# Auxboardone.net
KiCad netlist of a schematic drawn in Altium Designer
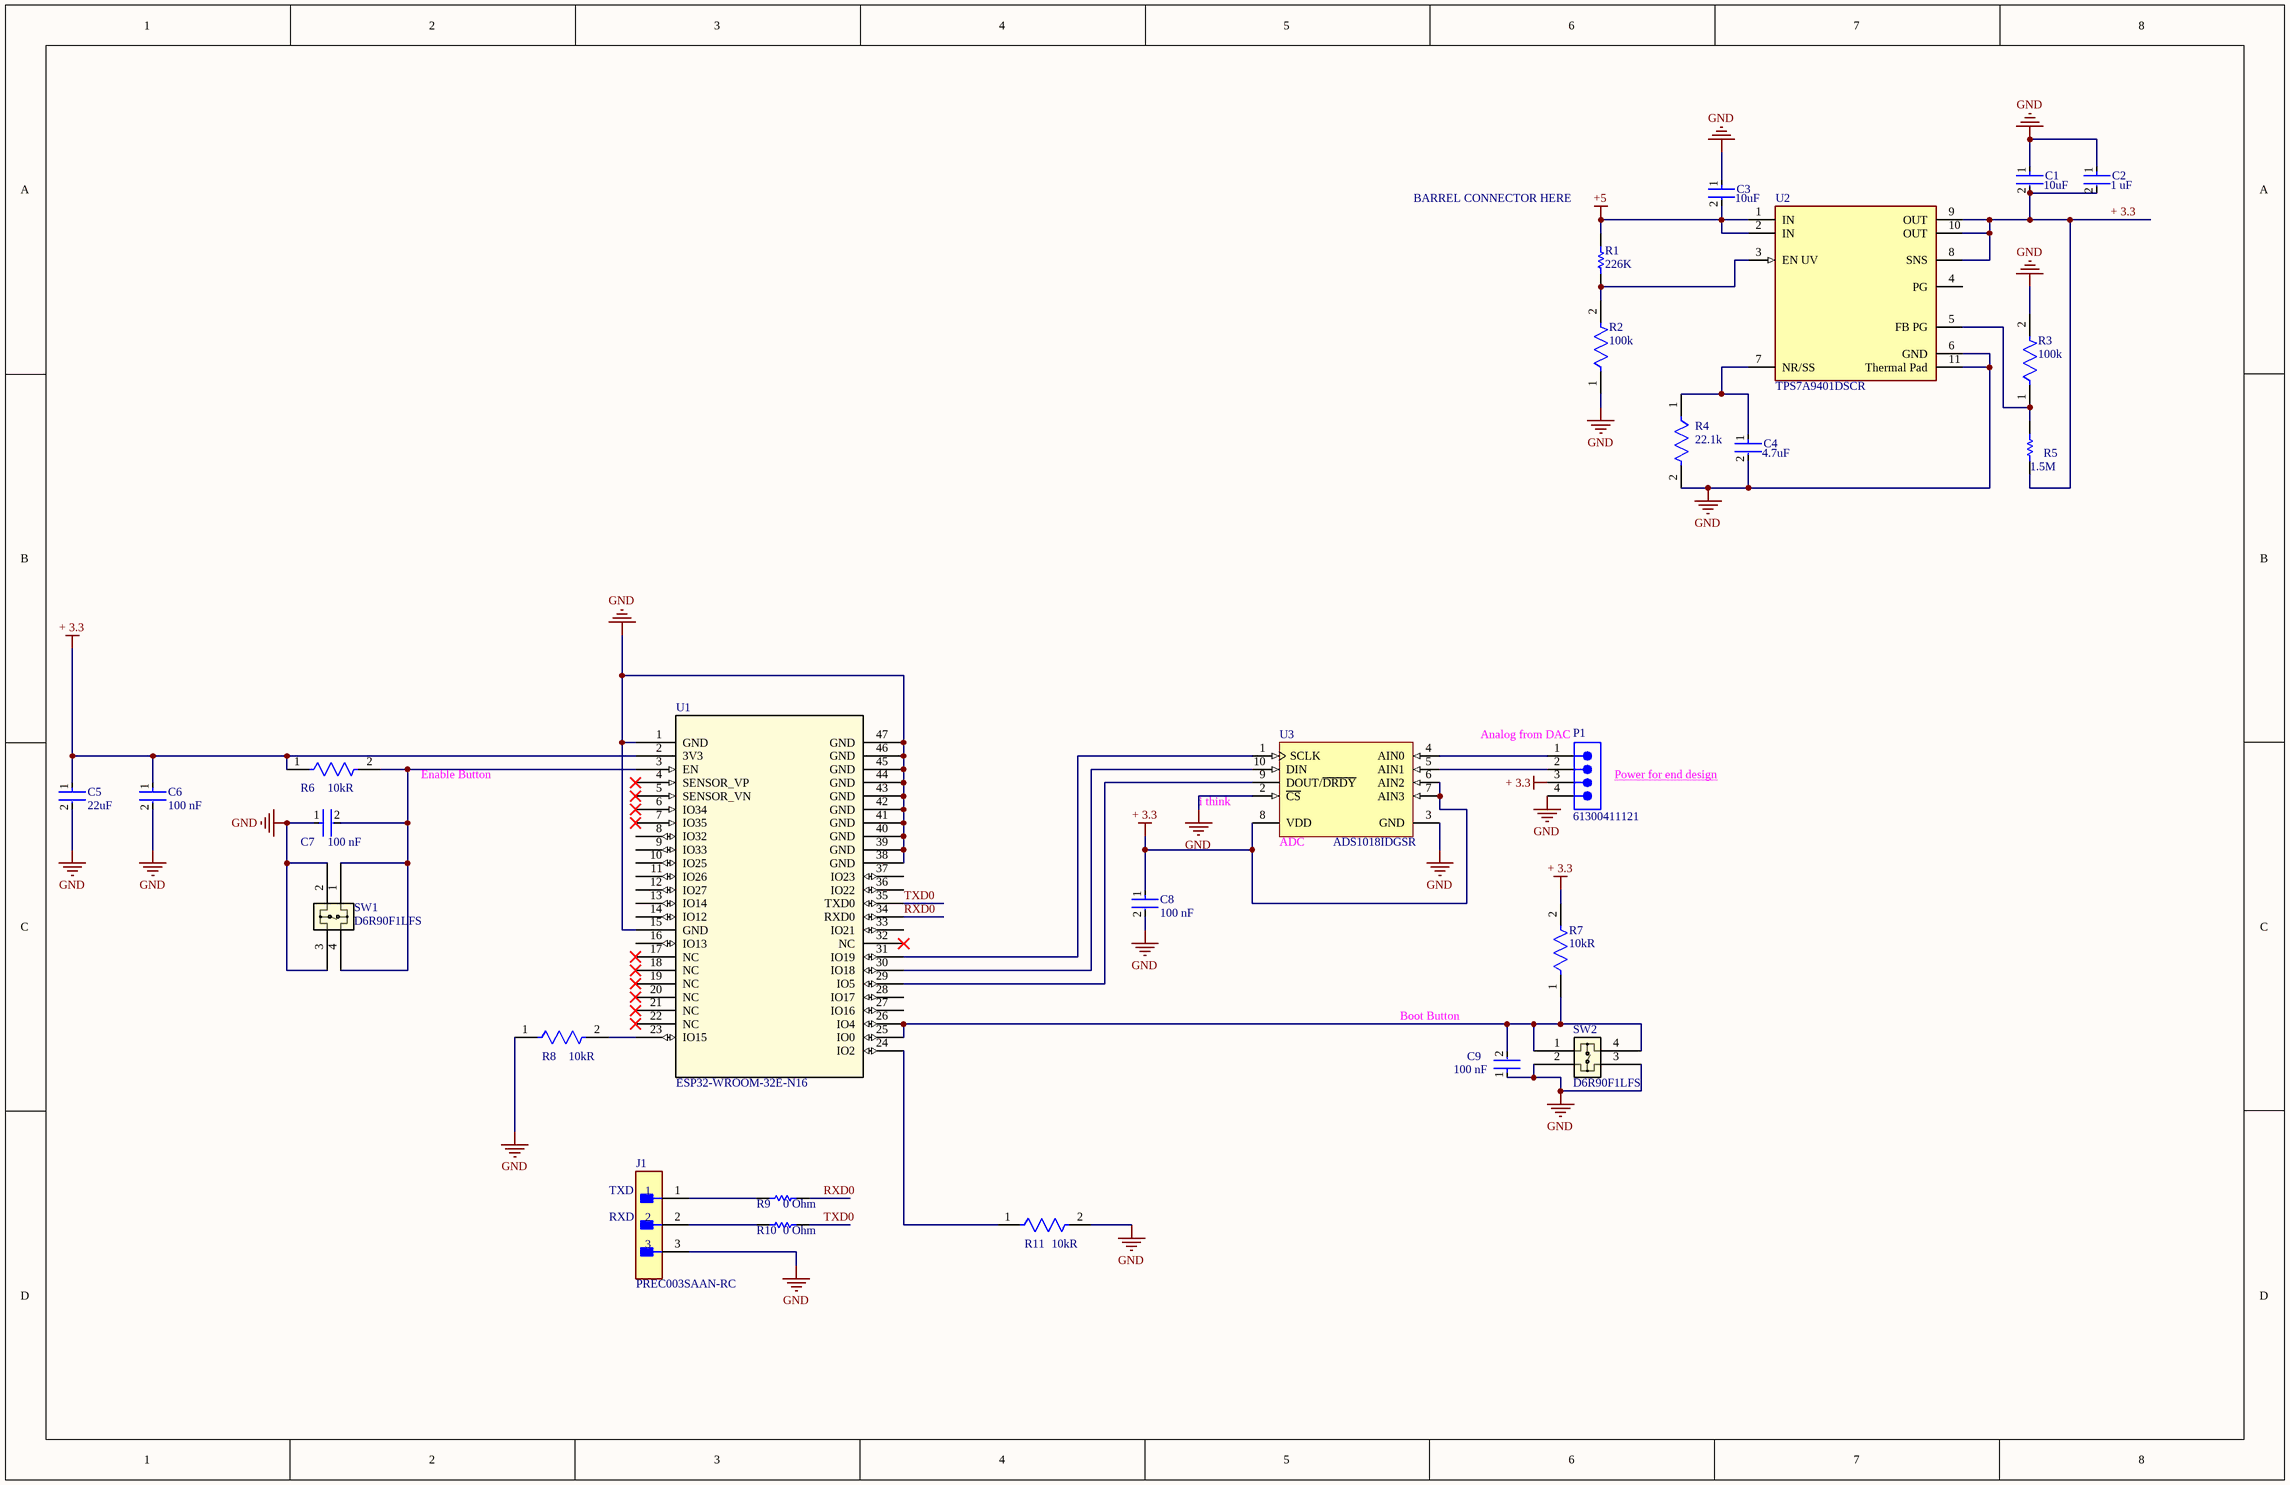
[diagram p0: Auxboardone.SchDoc]

(export (version "E")
  (design (tool "Eeschema 10.0.6"))
  (components
    (comp (ref "C1")
      (value "CL21A106KOQNNNE")
      (footprint "FP-CL21-IPC_B")
      (description "CL21 Series 0805 10uF 16V ±10% Tolerance X5R Multilayer Ceramic Chip Capacitor")
      (fields
        (field (name "VOLTAGE") "16V")
        (field (name "CAPACITANCE") "10uF")
        (field (name "TOLERANCE") "10%")
      )
      (libsource (lib "Altium Content Vault") (part "b4654b650e69147ec39a6b967a45e02"))
    )
    (comp (ref "C2")
      (value "CC0805KKX7R7BB105")
      (footprint "FP-CC0805-0_85-MFG")
      (description "CC0805 1 uF X7R 10.00% 16 V")
      (fields (field (name "CAPACITANCE") "1 uF") (field (name "MANUFACTURER") "Yageo"))
      (libsource (lib "Altium Content Vault") (part "11868f565c42a9108669ba33697ecf6"))
    )
    (comp (ref "C3")
      (value "CL21A106KOQNNNE")
      (footprint "FP-CL21-IPC_B")
      (description "CL21 Series 0805 10uF 16V ±10% Tolerance X5R Multilayer Ceramic Chip Capacitor")
      (fields
        (field (name "VOLTAGE") "16V")
        (field (name "CAPACITANCE") "10uF")
        (field (name "TOLERANCE") "10%")
      )
      (libsource (lib "Altium Content Vault") (part "b4654b650e69147ec39a6b967a45e02"))
    )
    (comp (ref "C4")
      (value "CL21A475KAQNNNE")
      (footprint "FP-CL21-IPC_A")
      (description "CL21 Series 0805 4.7uF 25V ±10% Tolerance X5R Multilayer Ceramic Chip Capacitor")
      (fields (field (name "CAPACITANCE") "4.7uF") (field (name "TOLERANCE") "10%"))
      (libsource (lib "Altium Content Vault") (part "b4654b650e69147ec39a6b967a45e02"))
    )
    (comp (ref "C5")
      (value "CL21A226MQQNNNE")
      (footprint "FP-CL21-IPC_A")
      (description "CL21 Series 0805 22uF 6.3V ±20% Tolerance X5R Multilayer Ceramic Chip Capacitor")
      (fields (field (name "CAPACITANCE") "22uF") (field (name "TOLERANCE") "20%"))
      (libsource (lib "Altium Content Vault") (part "b4654b650e69147ec39a6b967a45e02"))
    )
    (comp (ref "C6")
      (value "CC0805KRX7R9BB104")
      (footprint "FP-CC0805-0_85-MFG")
      (description "CAP CER 0.1UF 50V X7R 0805")
      (fields
        (field (name "TOLERANCE") "0.1")
        (field (name "CAPACITANCE") "100 nF")
        (field (name "MANUFACTURER") "Yageo")
      )
      (libsource (lib "Altium Content Vault") (part "11868f565c42a9108669ba33697ecf6"))
    )
    (comp (ref "C7")
      (value "CC0805KRX7R9BB104")
      (footprint "FP-CC0805-0_85-MFG")
      (description "CAP CER 0.1UF 50V X7R 0805")
      (fields
        (field (name "TOLERANCE") "0.1")
        (field (name "CAPACITANCE") "100 nF")
        (field (name "MANUFACTURER") "Yageo")
      )
      (libsource (lib "Altium Content Vault") (part "11868f565c42a9108669ba33697ecf6"))
    )
    (comp (ref "C8")
      (value "CC0805KRX7R9BB104")
      (footprint "FP-CC0805-0_85-MFG")
      (description "CAP CER 0.1UF 50V X7R 0805")
      (fields
        (field (name "TOLERANCE") "0.1")
        (field (name "CAPACITANCE") "100 nF")
        (field (name "MANUFACTURER") "Yageo")
      )
      (libsource (lib "Altium Content Vault") (part "11868f565c42a9108669ba33697ecf6"))
    )
    (comp (ref "C9")
      (value "CC0805KRX7R9BB104")
      (footprint "FP-CC0805-0_85-MFG")
      (description "CAP CER 0.1UF 50V X7R 0805")
      (fields
        (field (name "TOLERANCE") "0.1")
        (field (name "CAPACITANCE") "100 nF")
        (field (name "MANUFACTURER") "Yageo")
      )
      (libsource (lib "Altium Content Vault") (part "11868f565c42a9108669ba33697ecf6"))
    )
    (comp (ref "J1")
      (value "PREC003SAAN-RC")
      (footprint "FP-PREC003SAAN-RC-MFG")
      (description "PREC003SAAN-RC Conn Header Vert 3POS 2.54MM")
      (libsource (lib "Altium Content Vault") (part "0d3f023dd272f625e17a2be33dea85f"))
    )
    (comp (ref "P1")
      (value "61300411121")
      (footprint "61300411121")
      (libsource (lib "Altium Content Vault") (part "Header_Male_1R_04P"))
    )
    (comp (ref "R1")
      (value "RC0805FR-07226KL")
      (footprint "RESC2013X60X35LL10T20")
      (fields (field (name "MANUFACTURER") "Yageo") (field (name "RESISTANCE") "226K"))
      (libsource (lib "Altium Content Vault") (part "RES"))
    )
    (comp (ref "R2")
      (value "RC0805FR-07100KL")
      (footprint "FP-RC0805-0_6-IPC_C")
      (description "RES 100K OHM 1% 1/8W 0805")
      (fields (field (name "TOLERANCE") "1%") (field (name "RESISTANCE") "100k"))
      (libsource (lib "Altium Content Vault") (part "1029c3af85768c4190bb7ad29bc67b5"))
    )
    (comp (ref "R3")
      (value "RC0805FR-07100KL")
      (footprint "FP-RC0805-0_6-IPC_C")
      (description "RES 100K OHM 1% 1/8W 0805")
      (fields (field (name "TOLERANCE") "1%") (field (name "RESISTANCE") "100k"))
      (libsource (lib "Altium Content Vault") (part "1029c3af85768c4190bb7ad29bc67b5"))
    )
    (comp (ref "R4")
      (value "RMCF0805FT22K1")
      (footprint "FP-RMCF0805-IPC_B")
      (description "22.1kΩ ±1% 0.125W 0805 Thick Film Chip Resistor AEC-Q200 compliant")
      (fields (field (name "RESISTANCE") "22.1k") (field (name "TOLERANCE") "1%"))
      (libsource (lib "Altium Content Vault") (part "1029c3af85768c4190bb7ad29bc67b5"))
    )
    (comp (ref "R5")
      (value "1.5M")
      (footprint "RESC0805(2012)_N")
      (description "1M5 0.125W 5% 0805 (2012 Metric)  SMD")
      (fields (field (name "TOLERANCE") "5 %") (field (name "POWER") "0.125 W"))
      (libsource (lib "Altium Content Vault") (part "RES"))
    )
    (comp (ref "R6")
      (value "RR1220P-103-D")
      (footprint "FP-RR1220-IPC_A")
      (description "10kΩ ±0.5% 0.1W 1/10W Chip Resistor 0805 (2012 Metric) Thin Film")
      (fields (field (name "RESISTANCE") "10kR") (field (name "TOLERANCE") "0.5%"))
      (libsource (lib "Altium Content Vault") (part "1029c3af85768c4190bb7ad29bc67b5"))
    )
    (comp (ref "R7")
      (value "RR1220P-103-D")
      (footprint "FP-RR1220-IPC_A")
      (description "10kΩ ±0.5% 0.1W 1/10W Chip Resistor 0805 (2012 Metric) Thin Film")
      (fields (field (name "RESISTANCE") "10kR") (field (name "TOLERANCE") "0.5%"))
      (libsource (lib "Altium Content Vault") (part "1029c3af85768c4190bb7ad29bc67b5"))
    )
    (comp (ref "R8")
      (value "RR1220P-103-D")
      (footprint "FP-RR1220-IPC_A")
      (description "10kΩ ±0.5% 0.1W 1/10W Chip Resistor 0805 (2012 Metric) Thin Film")
      (fields (field (name "RESISTANCE") "10kR") (field (name "TOLERANCE") "0.5%"))
      (libsource (lib "Altium Content Vault") (part "1029c3af85768c4190bb7ad29bc67b5"))
    )
    (comp (ref "R9")
      (value "ERJ-6GEY0R00V")
      (footprint "RESC2013X70X40NL20T20")
      (description "Chip Resistor, 0 Ohm, +/- 1%, 0.125 W, -55 to 155 degC, 0805 (2012 Metric), RoHS, Tape and Reel")
      (fields (field (name "TOLERANCE") "5%") (field (name "RESISTANCE") "0 Ohm"))
      (libsource (lib "Altium Content Vault") (part "RES-2"))
    )
    (comp (ref "R10")
      (value "ERJ-6GEY0R00V")
      (footprint "RESC2013X70X40NL20T20")
      (description "Chip Resistor, 0 Ohm, +/- 1%, 0.125 W, -55 to 155 degC, 0805 (2012 Metric), RoHS, Tape and Reel")
      (fields (field (name "TOLERANCE") "5%") (field (name "RESISTANCE") "0 Ohm"))
      (libsource (lib "Altium Content Vault") (part "RES-2"))
    )
    (comp (ref "R11")
      (value "RR1220P-103-D")
      (footprint "FP-RR1220-IPC_A")
      (description "10kΩ ±0.5% 0.1W 1/10W Chip Resistor 0805 (2012 Metric) Thin Film")
      (fields (field (name "RESISTANCE") "10kR") (field (name "TOLERANCE") "0.5%"))
      (libsource (lib "Altium Content Vault") (part "1029c3af85768c4190bb7ad29bc67b5"))
    )
    (comp (ref "SW1")
      (value "D6R90F1LFS")
      (footprint "D6R_CNK")
      (description "No Description Available")
      (libsource (lib "") (part "D6R90F1LFS_1"))
    )
    (comp (ref "SW2")
      (value "D6R90F1LFS")
      (footprint "D6R_CNK")
      (description "No Description Available")
      (libsource (lib "Button") (part "D6R90F1LFS"))
    )
    (comp (ref "U1")
      (value "ESP32-WROOM-32E-N16")
      (footprint "ESP32-WROOM-32E_EXP")
      (description "No Description Available")
      (libsource (lib "ESP32-WROOM-32E-N16") (part "ESP32-WROOM-32E-N16"))
    )
    (comp (ref "U2")
      (value "TPS7A9401DSCR")
      (footprint "FP-DSC0010J-MFG")
      (description "1-A, ULTRA-LOW NOISE, ULTRA-HIGH")
      (libsource (lib "Altium Content Vault") (part "a6308bcaf518fe2c6c22e77077fd2b2"))
    )
    (comp (ref "U3")
      (value "ADS1018IDGSR")
      (footprint "TI-DGS10_N")
      (fields (field (name "MANUFACTURER") "Texas Instruments"))
      (libsource (lib "Altium Content Vault") (part "TI-ADS1X18XXX10"))
    )
  )
  (nets
    (net (code "1") (name "+ 3.3") (class "Default")
      (node (ref "C1") (pin "2") (pinfunction "2_2") (pintype "passive"))
      (node (ref "C2") (pin "2") (pinfunction "2_2") (pintype "passive"))
      (node (ref "C5") (pin "1") (pinfunction "1_1") (pintype "passive"))
      (node (ref "C6") (pin "1") (pinfunction "1_1") (pintype "passive"))
      (node (ref "C8") (pin "1") (pinfunction "1_1") (pintype "passive"))
      (node (ref "P1") (pin "3") (pinfunction "3_3") (pintype "passive"))
      (node (ref "R5") (pin "1") (pinfunction "1_1") (pintype "passive"))
      (node (ref "R6") (pin "1") (pinfunction "1_1") (pintype "passive"))
      (node (ref "R7") (pin "2") (pinfunction "2_2") (pintype "passive"))
      (node (ref "U1") (pin "2") (pinfunction "3V3_2") (pintype "power_in"))
      (node (ref "U2") (pin "10") (pinfunction "OUT_10") (pintype "power_in"))
      (node (ref "U2") (pin "8") (pinfunction "SNS_8") (pintype "passive"))
      (node (ref "U2") (pin "9") (pinfunction "OUT_9") (pintype "power_in"))
      (node (ref "U3") (pin "6") (pinfunction "AIN2_6") (pintype "input"))
      (node (ref "U3") (pin "7") (pinfunction "AIN3_7") (pintype "input"))
      (node (ref "U3") (pin "8") (pinfunction "VDD_8") (pintype "power_in"))
    )
    (net (code "2") (name "+5") (class "Default")
      (node (ref "C3") (pin "2") (pinfunction "2_2") (pintype "passive"))
      (node (ref "R1") (pin "2") (pinfunction "2_2") (pintype "passive"))
      (node (ref "U2") (pin "1") (pinfunction "IN_1") (pintype "power_in"))
      (node (ref "U2") (pin "2") (pinfunction "IN_2") (pintype "power_in"))
    )
    (net (code "3") (name "/RXD0") (class "Default")
      (node (ref "R9") (pin "2") (pinfunction "2_2") (pintype "passive"))
      (node (ref "U1") (pin "34") (pinfunction "RXD0_34") (pintype "bidirectional"))
    )
    (net (code "4") (name "/TXD0") (class "Default")
      (node (ref "R10") (pin "2") (pinfunction "2_2") (pintype "passive"))
      (node (ref "U1") (pin "35") (pinfunction "TXD0_35") (pintype "bidirectional"))
    )
    (net (code "5") (name "GND") (class "Default")
      (node (ref "C1") (pin "1") (pinfunction "1_1") (pintype "passive"))
      (node (ref "C2") (pin "1") (pinfunction "1_1") (pintype "passive"))
      (node (ref "C3") (pin "1") (pinfunction "1_1") (pintype "passive"))
      (node (ref "C4") (pin "2") (pinfunction "2_2") (pintype "passive"))
      (node (ref "C5") (pin "2") (pinfunction "2_2") (pintype "passive"))
      (node (ref "C6") (pin "2") (pinfunction "2_2") (pintype "passive"))
      (node (ref "C7") (pin "1") (pinfunction "1_1") (pintype "passive"))
      (node (ref "C8") (pin "2") (pinfunction "2_2") (pintype "passive"))
      (node (ref "C9") (pin "1") (pinfunction "1_1") (pintype "passive"))
      (node (ref "J1") (pin "3") (pinfunction "3_3") (pintype "passive"))
      (node (ref "P1") (pin "4") (pinfunction "4_4") (pintype "passive"))
      (node (ref "R11") (pin "2") (pinfunction "2_2") (pintype "passive"))
      (node (ref "R2") (pin "1") (pinfunction "1_1") (pintype "passive"))
      (node (ref "R3") (pin "2") (pinfunction "2_2") (pintype "passive"))
      (node (ref "R4") (pin "2") (pinfunction "2_2") (pintype "passive"))
      (node (ref "R8") (pin "1") (pinfunction "1_1") (pintype "passive"))
      (node (ref "SW1") (pin "2") (pinfunction "2_2") (pintype "passive"))
      (node (ref "SW1") (pin "3") (pinfunction "3_3") (pintype "passive"))
      (node (ref "SW2") (pin "2") (pinfunction "2_2") (pintype "passive"))
      (node (ref "SW2") (pin "3") (pinfunction "3_3") (pintype "passive"))
      (node (ref "U1") (pin "1") (pinfunction "GND_1") (pintype "power_in"))
      (node (ref "U1") (pin "15") (pinfunction "GND_15") (pintype "power_in"))
      (node (ref "U1") (pin "38") (pinfunction "GND_38") (pintype "power_in"))
      (node (ref "U1") (pin "39") (pinfunction "GND_39") (pintype "power_in"))
      (node (ref "U1") (pin "40") (pinfunction "GND_40") (pintype "power_in"))
      (node (ref "U1") (pin "41") (pinfunction "GND_41") (pintype "power_in"))
      (node (ref "U1") (pin "42") (pinfunction "GND_42") (pintype "power_in"))
      (node (ref "U1") (pin "43") (pinfunction "GND_43") (pintype "power_in"))
      (node (ref "U1") (pin "44") (pinfunction "GND_44") (pintype "power_in"))
      (node (ref "U1") (pin "45") (pinfunction "GND_45") (pintype "power_in"))
      (node (ref "U1") (pin "46") (pinfunction "GND_46") (pintype "power_in"))
      (node (ref "U1") (pin "47") (pinfunction "GND_47") (pintype "power_in"))
      (node (ref "U2") (pin "11") (pinfunction "Thermal_Pad_11") (pintype "power_in"))
      (node (ref "U2") (pin "6") (pinfunction "GND_6") (pintype "power_in"))
      (node (ref "U3") (pin "2") (pinfunction "~{CS}_2") (pintype "input"))
      (node (ref "U3") (pin "3") (pinfunction "GND_3") (pintype "power_in"))
    )
    (net (code "6") (name "Net-(J1-Pad1)") (class "Default")
      (node (ref "J1") (pin "1") (pinfunction "1_1") (pintype "passive"))
      (node (ref "R9") (pin "1") (pinfunction "1_1") (pintype "passive"))
    )
    (net (code "7") (name "Net-(J1-Pad2)") (class "Default")
      (node (ref "J1") (pin "2") (pinfunction "2_2") (pintype "passive"))
      (node (ref "R10") (pin "1") (pinfunction "1_1") (pintype "passive"))
    )
    (net (code "8") (name "Net-(U1-EN)") (class "Default")
      (node (ref "C7") (pin "2") (pinfunction "2_2") (pintype "passive"))
      (node (ref "R6") (pin "2") (pinfunction "2_2") (pintype "passive"))
      (node (ref "SW1") (pin "1") (pinfunction "1_1") (pintype "passive"))
      (node (ref "SW1") (pin "4") (pinfunction "4_4") (pintype "passive"))
      (node (ref "U1") (pin "3") (pinfunction "EN_3") (pintype "input"))
    )
    (net (code "9") (name "Net-(U1-IO0)") (class "Default")
      (node (ref "C9") (pin "2") (pinfunction "2_2") (pintype "passive"))
      (node (ref "R7") (pin "1") (pinfunction "1_1") (pintype "passive"))
      (node (ref "SW2") (pin "1") (pinfunction "1_1") (pintype "passive"))
      (node (ref "SW2") (pin "4") (pinfunction "4_4") (pintype "passive"))
      (node (ref "U1") (pin "25") (pinfunction "IO0_25") (pintype "bidirectional"))
      (node (ref "U1") (pin "26") (pinfunction "IO4_26") (pintype "bidirectional"))
    )
    (net (code "10") (name "Net-(U1-IO2)") (class "Default")
      (node (ref "R11") (pin "1") (pinfunction "1_1") (pintype "passive"))
      (node (ref "U1") (pin "24") (pinfunction "IO2_24") (pintype "bidirectional"))
    )
    (net (code "11") (name "Net-(U1-IO5)") (class "Default")
      (node (ref "U1") (pin "29") (pinfunction "IO5_29") (pintype "bidirectional"))
      (node (ref "U3") (pin "9") (pinfunction "DOUT/~{DRDY}_9") (pintype "tri_state"))
    )
    (net (code "12") (name "Net-(U1-IO15)") (class "Default")
      (node (ref "R8") (pin "2") (pinfunction "2_2") (pintype "passive"))
      (node (ref "U1") (pin "23") (pinfunction "IO15_23") (pintype "bidirectional"))
    )
    (net (code "13") (name "Net-(U1-IO18)") (class "Default")
      (node (ref "U1") (pin "30") (pinfunction "IO18_30") (pintype "bidirectional"))
      (node (ref "U3") (pin "10") (pinfunction "DIN_10") (pintype "input"))
    )
    (net (code "14") (name "Net-(U1-IO19)") (class "Default")
      (node (ref "U1") (pin "31") (pinfunction "IO19_31") (pintype "bidirectional"))
      (node (ref "U3") (pin "1") (pinfunction "SCLK_1") (pintype "input"))
    )
    (net (code "15") (name "Net-(U2-EN_UV)") (class "Default")
      (node (ref "R1") (pin "1") (pinfunction "1_1") (pintype "passive"))
      (node (ref "R2") (pin "2") (pinfunction "2_2") (pintype "passive"))
      (node (ref "U2") (pin "3") (pinfunction "EN_UV_3") (pintype "input"))
    )
    (net (code "16") (name "Net-(U2-FB_PG)") (class "Default")
      (node (ref "R3") (pin "1") (pinfunction "1_1") (pintype "passive"))
      (node (ref "R5") (pin "2") (pinfunction "2_2") (pintype "passive"))
      (node (ref "U2") (pin "5") (pinfunction "FB_PG_5") (pintype "passive"))
    )
    (net (code "17") (name "Net-(U2-NR{slash}SS)") (class "Default")
      (node (ref "C4") (pin "1") (pinfunction "1_1") (pintype "passive"))
      (node (ref "R4") (pin "1") (pinfunction "1_1") (pintype "passive"))
      (node (ref "U2") (pin "7") (pinfunction "NR/SS_7") (pintype "passive"))
    )
    (net (code "18") (name "Net-(U3-AIN0)") (class "Default")
      (node (ref "P1") (pin "1") (pinfunction "1_1") (pintype "passive"))
      (node (ref "U3") (pin "4") (pinfunction "AIN0_4") (pintype "input"))
    )
    (net (code "19") (name "Net-(U3-AIN1)") (class "Default")
      (node (ref "P1") (pin "2") (pinfunction "2_2") (pintype "passive"))
      (node (ref "U3") (pin "5") (pinfunction "AIN1_5") (pintype "input"))
    )
    (net (code "20") (name "unconnected-(U1-IO12-Pad14)") (class "Default")
      (node (ref "U1") (pin "14") (pinfunction "IO12_14") (pintype "bidirectional"))
    )
    (net (code "21") (name "unconnected-(U1-IO13-Pad16)") (class "Default")
      (node (ref "U1") (pin "16") (pinfunction "IO13_16") (pintype "bidirectional"))
    )
    (net (code "22") (name "unconnected-(U1-IO14-Pad13)") (class "Default")
      (node (ref "U1") (pin "13") (pinfunction "IO14_13") (pintype "bidirectional"))
    )
    (net (code "23") (name "unconnected-(U1-IO16-Pad27)") (class "Default")
      (node (ref "U1") (pin "27") (pinfunction "IO16_27") (pintype "bidirectional"))
    )
    (net (code "24") (name "unconnected-(U1-IO17-Pad28)") (class "Default")
      (node (ref "U1") (pin "28") (pinfunction "IO17_28") (pintype "bidirectional"))
    )
    (net (code "25") (name "unconnected-(U1-IO21-Pad33)") (class "Default")
      (node (ref "U1") (pin "33") (pinfunction "IO21_33") (pintype "bidirectional"))
    )
    (net (code "26") (name "unconnected-(U1-IO22-Pad36)") (class "Default")
      (node (ref "U1") (pin "36") (pinfunction "IO22_36") (pintype "bidirectional"))
    )
    (net (code "27") (name "unconnected-(U1-IO23-Pad37)") (class "Default")
      (node (ref "U1") (pin "37") (pinfunction "IO23_37") (pintype "bidirectional"))
    )
    (net (code "28") (name "unconnected-(U1-IO25-Pad10)") (class "Default")
      (node (ref "U1") (pin "10") (pinfunction "IO25_10") (pintype "bidirectional"))
    )
    (net (code "29") (name "unconnected-(U1-IO26-Pad11)") (class "Default")
      (node (ref "U1") (pin "11") (pinfunction "IO26_11") (pintype "bidirectional"))
    )
    (net (code "30") (name "unconnected-(U1-IO27-Pad12)") (class "Default")
      (node (ref "U1") (pin "12") (pinfunction "IO27_12") (pintype "bidirectional"))
    )
    (net (code "31") (name "unconnected-(U1-IO32-Pad8)") (class "Default")
      (node (ref "U1") (pin "8") (pinfunction "IO32_8") (pintype "bidirectional"))
    )
    (net (code "32") (name "unconnected-(U1-IO33-Pad9)") (class "Default")
      (node (ref "U1") (pin "9") (pinfunction "IO33_9") (pintype "bidirectional"))
    )
    (net (code "33") (name "unconnected-(U1-IO34-Pad6)") (class "Default")
      (node (ref "U1") (pin "6") (pinfunction "IO34_6") (pintype "input+no_connect"))
    )
    (net (code "34") (name "unconnected-(U1-IO35-Pad7)") (class "Default")
      (node (ref "U1") (pin "7") (pinfunction "IO35_7") (pintype "input+no_connect"))
    )
    (net (code "35") (name "unconnected-(U1-NC-Pad17)") (class "Default")
      (node (ref "U1") (pin "17") (pinfunction "NC_17") (pintype "passive+no_connect"))
    )
    (net (code "36") (name "unconnected-(U1-NC-Pad18)") (class "Default")
      (node (ref "U1") (pin "18") (pinfunction "NC_18") (pintype "passive+no_connect"))
    )
    (net (code "37") (name "unconnected-(U1-NC-Pad19)") (class "Default")
      (node (ref "U1") (pin "19") (pinfunction "NC_19") (pintype "passive+no_connect"))
    )
    (net (code "38") (name "unconnected-(U1-NC-Pad20)") (class "Default")
      (node (ref "U1") (pin "20") (pinfunction "NC_20") (pintype "passive+no_connect"))
    )
    (net (code "39") (name "unconnected-(U1-NC-Pad21)") (class "Default")
      (node (ref "U1") (pin "21") (pinfunction "NC_21") (pintype "passive+no_connect"))
    )
    (net (code "40") (name "unconnected-(U1-NC-Pad22)") (class "Default")
      (node (ref "U1") (pin "22") (pinfunction "NC_22") (pintype "passive+no_connect"))
    )
    (net (code "41") (name "unconnected-(U1-NC-Pad32)") (class "Default")
      (node (ref "U1") (pin "32") (pinfunction "NC_32") (pintype "passive+no_connect"))
    )
    (net (code "42") (name "unconnected-(U1-SENSOR_VN-Pad5)") (class "Default")
      (node (ref "U1") (pin "5") (pinfunction "SENSOR_VN_5") (pintype "input+no_connect"))
    )
    (net (code "43") (name "unconnected-(U1-SENSOR_VP-Pad4)") (class "Default")
      (node (ref "U1") (pin "4") (pinfunction "SENSOR_VP_4") (pintype "input+no_connect"))
    )
    (net (code "44") (name "unconnected-(U2-PG-Pad4)") (class "Default")
      (node (ref "U2") (pin "4") (pinfunction "PG_4") (pintype "open_collector"))
    )
  )
)
